# DM2097_Connector_B.net
KiCad netlist of a schematic drawn in Altium Designer
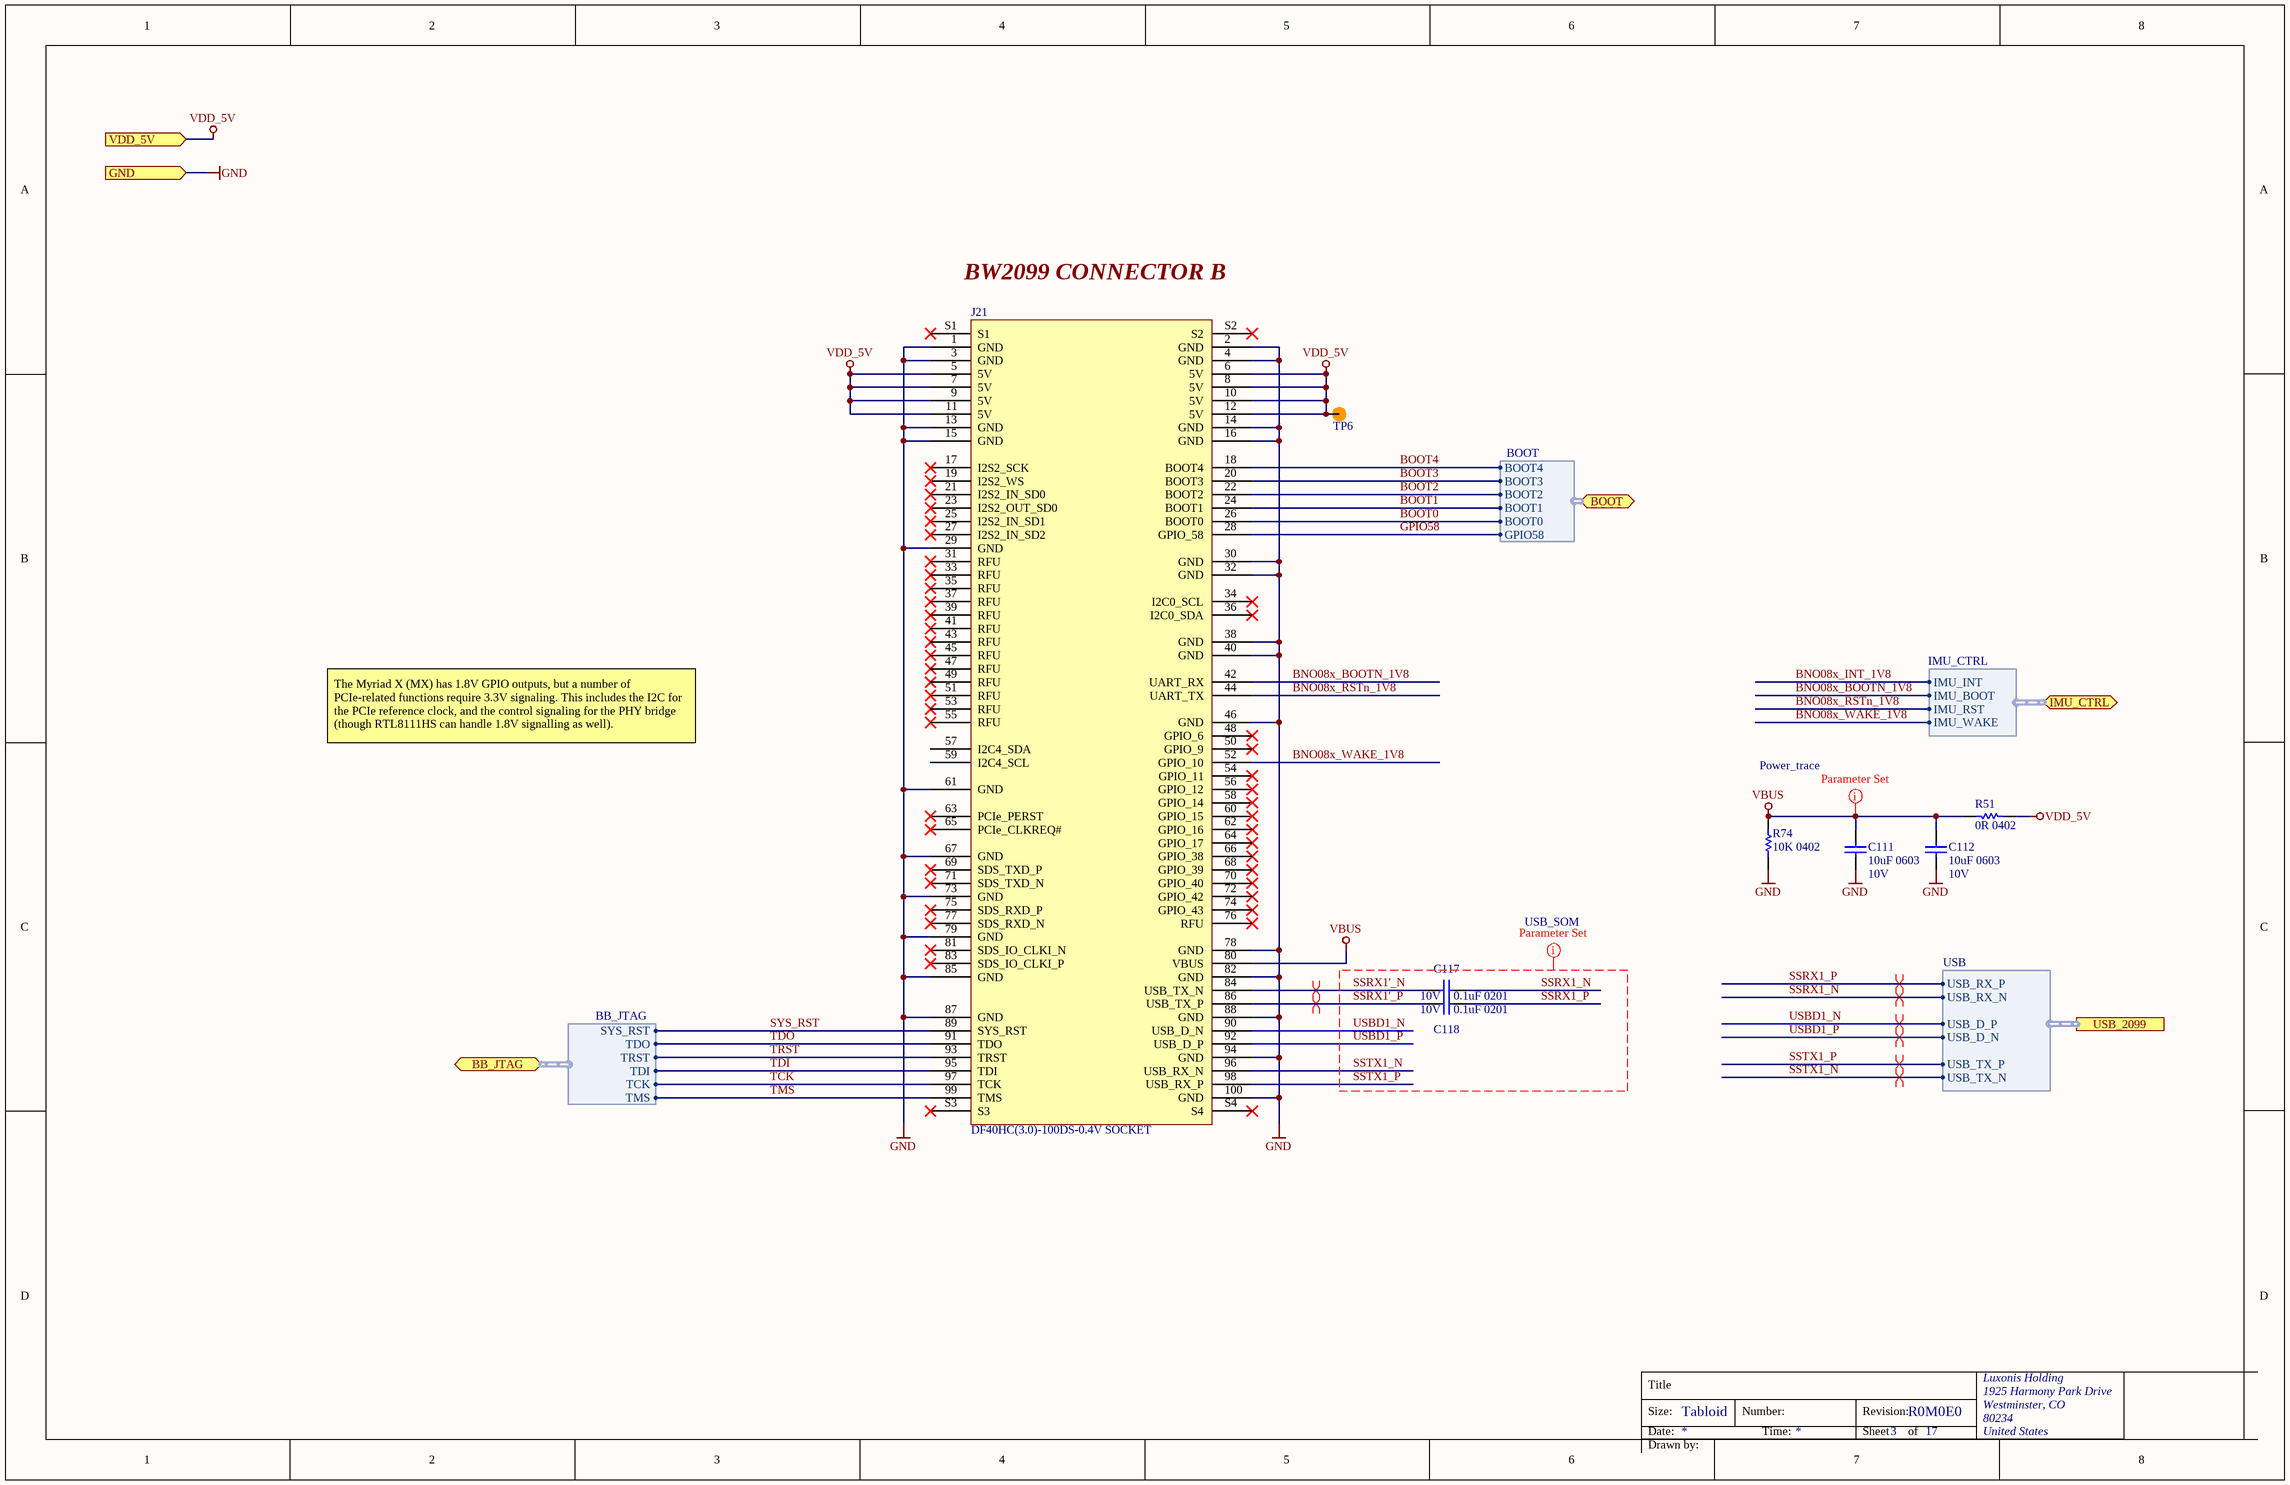
[diagram p0: DM2097_Connector_B.SchDoc]

(export (version "E")
  (design (tool "Eeschema 10.0.6"))
  (components
    (comp (ref "C111")
      (value "10uF 0603")
      (footprint "CAP_Altium_Vault_Generic:CAPC0603(1608)100_N")
      (description "CAP CER 10UF 10V X5R 0603 20%")
      (fields (field (name "TOLERANCE") "20%") (field (name "VOLTAGE RATING") "10V"))
      (libsource (lib "LuxonisMaster") (part "GRM188R61A106ME69D"))
    )
    (comp (ref "C112")
      (value "10uF 0603")
      (footprint "CAP_Altium_Vault_Generic:CAPC0603(1608)100_N")
      (description "CAP CER 10UF 10V X5R 0603 20%")
      (fields (field (name "TOLERANCE") "20%") (field (name "VOLTAGE RATING") "10V"))
      (libsource (lib "LuxonisMaster") (part "GRM188R61A106ME69D"))
    )
    (comp (ref "C117")
      (value "0.1uF 0201")
      (footprint "CAP_Altium_Vault_Generic:CAPC0201(0603)33_L")
      (description "CAP CER 0.1UF 10V X5R 0201")
      (fields (field (name "TOLERANCE") "10%") (field (name "VOLTAGE") "10V"))
      (libsource (lib "LuxonisMaster") (part "GRM033R61A104KE15D"))
    )
    (comp (ref "C118")
      (value "0.1uF 0201")
      (footprint "CAP_Altium_Vault_Generic:CAPC0201(0603)33_L")
      (description "CAP CER 0.1UF 10V X5R 0201")
      (fields (field (name "TOLERANCE") "10%") (field (name "VOLTAGE") "10V"))
      (libsource (lib "LuxonisMaster") (part "GRM033R61A104KE15D"))
    )
    (comp (ref "J21")
      (value "DF40HC(3.0)-100DS-0.4V SOCKET")
      (footprint "DF40HC-3.0-100DS-0.4V_minpad")
      (description "Conn Board to Board RCP 100 POS 0.4mm Solder ST SMD T/R")
      (libsource (lib "LuxonisMaster_OPAL") (part "BW2099_SCKT_Conn_B"))
    )
    (comp (ref "R51")
      (value "0R 0402")
      (footprint "RES_Altium_Vault_Generic:RESC0402(1005)_N")
      (description "RES SMD 0 OHM JUMPER 1/16W 0402")
      (fields (field (name "TOLERANCE") "5%"))
      (libsource (lib "LuxonisMaster") (part "CRCW04020000Z0ED"))
    )
    (comp (ref "R74")
      (value "10K 0402")
      (footprint "RES_Altium_Vault_Generic:RESC0402(1005)_N")
      (fields (field (name "TOLERANCE") "1%"))
      (libsource (lib "LuxonisMaster") (part "RC0402FR-1310KL"))
    )
    (comp (ref "TP6")
      (value "TP100_200_NS")
      (footprint "LuxonisMaster:TP100_200_NS")
      (libsource (lib "LuxonisMaster") (part "TEST_POINT"))
    )
  )
  (nets
    (net (code "5") (name "/BNO08x_BOOTN_1V8") (class "Default")
      (node (ref "J21") (pin "42") (pinfunction "UART_RX_42") (pintype "passive"))
    )
    (net (code "7") (name "/BNO08x_RSTn_1V8") (class "Default")
      (node (ref "J21") (pin "44") (pinfunction "UART_TX_44") (pintype "passive"))
    )
    (net (code "8") (name "/BNO08x_WAKE_1V8") (class "Default")
      (node (ref "J21") (pin "52") (pinfunction "GPIO_10_52") (pintype "passive"))
    )
    (net (code "9") (name "/BOOT0") (class "Default")
      (node (ref "J21") (pin "26") (pinfunction "BOOT0_26") (pintype "passive"))
    )
    (net (code "10") (name "/BOOT1") (class "Default")
      (node (ref "J21") (pin "24") (pinfunction "BOOT1_24") (pintype "passive"))
    )
    (net (code "11") (name "/BOOT2") (class "Default")
      (node (ref "J21") (pin "22") (pinfunction "BOOT2_22") (pintype "passive"))
    )
    (net (code "12") (name "/BOOT3") (class "Default")
      (node (ref "J21") (pin "20") (pinfunction "BOOT3_20") (pintype "passive"))
    )
    (net (code "13") (name "/BOOT4") (class "Default")
      (node (ref "J21") (pin "18") (pinfunction "BOOT4_18") (pintype "passive"))
    )
    (net (code "14") (name "/GPIO58") (class "Default")
      (node (ref "J21") (pin "28") (pinfunction "GPIO_58_28") (pintype "passive"))
    )
    (net (code "15") (name "/SSRX1'_N") (class "Default")
      (node (ref "C117") (pin "1") (pinfunction "1_1") (pintype "passive"))
      (node (ref "J21") (pin "84") (pinfunction "USB_TX_N_84") (pintype "passive"))
    )
    (net (code "16") (name "/SSRX1'_P") (class "Default")
      (node (ref "C118") (pin "1") (pinfunction "1_1") (pintype "passive"))
      (node (ref "J21") (pin "86") (pinfunction "USB_TX_P_86") (pintype "passive"))
    )
    (net (code "17") (name "/SSRX1_N") (class "Default")
      (node (ref "C117") (pin "2") (pinfunction "2_2") (pintype "passive"))
    )
    (net (code "18") (name "/SSRX1_P") (class "Default")
      (node (ref "C118") (pin "2") (pinfunction "2_2") (pintype "passive"))
    )
    (net (code "19") (name "/SSTX1_N") (class "Default")
      (node (ref "J21") (pin "96") (pinfunction "USB_RX_N_96") (pintype "passive"))
    )
    (net (code "20") (name "/SSTX1_P") (class "Default")
      (node (ref "J21") (pin "98") (pinfunction "USB_RX_P_98") (pintype "passive"))
    )
    (net (code "21") (name "/SYS_RST") (class "Default")
      (node (ref "J21") (pin "89") (pinfunction "SYS_RST_89") (pintype "passive"))
    )
    (net (code "22") (name "/TCK") (class "Default")
      (node (ref "J21") (pin "97") (pinfunction "TCK_97") (pintype "passive"))
    )
    (net (code "23") (name "/TDI") (class "Default")
      (node (ref "J21") (pin "95") (pinfunction "TDI_95") (pintype "passive"))
    )
    (net (code "24") (name "/TDO") (class "Default")
      (node (ref "J21") (pin "91") (pinfunction "TDO_91") (pintype "passive"))
    )
    (net (code "25") (name "/TMS") (class "Default")
      (node (ref "J21") (pin "99") (pinfunction "TMS_99") (pintype "passive"))
    )
    (net (code "26") (name "/TRST") (class "Default")
      (node (ref "J21") (pin "93") (pinfunction "TRST_93") (pintype "passive"))
    )
    (net (code "27") (name "/USBD1_N") (class "Default")
      (node (ref "J21") (pin "90") (pinfunction "USB_D_N_90") (pintype "passive"))
    )
    (net (code "28") (name "/USBD1_P") (class "Default")
      (node (ref "J21") (pin "92") (pinfunction "USB_D_P_92") (pintype "passive"))
    )
    (net (code "33") (name "GND") (class "Default")
      (node (ref "C111") (pin "1") (pinfunction "1_1") (pintype "passive"))
      (node (ref "C112") (pin "1") (pinfunction "1_1") (pintype "passive"))
      (node (ref "J21") (pin "1") (pinfunction "GND_1") (pintype "passive"))
      (node (ref "J21") (pin "100") (pinfunction "GND_100") (pintype "passive"))
      (node (ref "J21") (pin "13") (pinfunction "GND_13") (pintype "passive"))
      (node (ref "J21") (pin "14") (pinfunction "GND_14") (pintype "passive"))
      (node (ref "J21") (pin "15") (pinfunction "GND_15") (pintype "passive"))
      (node (ref "J21") (pin "16") (pinfunction "GND_16") (pintype "passive"))
      (node (ref "J21") (pin "2") (pinfunction "GND_2") (pintype "passive"))
      (node (ref "J21") (pin "29") (pinfunction "GND_29") (pintype "passive"))
      (node (ref "J21") (pin "3") (pinfunction "GND_3") (pintype "passive"))
      (node (ref "J21") (pin "30") (pinfunction "GND_30") (pintype "passive"))
      (node (ref "J21") (pin "32") (pinfunction "GND_32") (pintype "passive"))
      (node (ref "J21") (pin "38") (pinfunction "GND_38") (pintype "passive"))
      (node (ref "J21") (pin "4") (pinfunction "GND_4") (pintype "passive"))
      (node (ref "J21") (pin "40") (pinfunction "GND_40") (pintype "passive"))
      (node (ref "J21") (pin "46") (pinfunction "GND_46") (pintype "passive"))
      (node (ref "J21") (pin "61") (pinfunction "GND_61") (pintype "passive"))
      (node (ref "J21") (pin "67") (pinfunction "GND_67") (pintype "passive"))
      (node (ref "J21") (pin "73") (pinfunction "GND_73") (pintype "passive"))
      (node (ref "J21") (pin "78") (pinfunction "GND_78") (pintype "passive"))
      (node (ref "J21") (pin "79") (pinfunction "GND_79") (pintype "passive"))
      (node (ref "J21") (pin "82") (pinfunction "GND_82") (pintype "passive"))
      (node (ref "J21") (pin "85") (pinfunction "GND_85") (pintype "passive"))
      (node (ref "J21") (pin "87") (pinfunction "GND_87") (pintype "passive"))
      (node (ref "J21") (pin "88") (pinfunction "GND_88") (pintype "passive"))
      (node (ref "J21") (pin "94") (pinfunction "GND_94") (pintype "passive"))
      (node (ref "R74") (pin "1") (pinfunction "1_1") (pintype "passive"))
    )
    (net (code "34") (name "VBUS") (class "Default")
      (node (ref "C111") (pin "2") (pinfunction "2_2") (pintype "passive"))
      (node (ref "C112") (pin "2") (pinfunction "2_2") (pintype "passive"))
      (node (ref "J21") (pin "80") (pinfunction "VBUS_80") (pintype "passive"))
      (node (ref "R51") (pin "1") (pinfunction "1_1") (pintype "passive"))
      (node (ref "R74") (pin "2") (pinfunction "2_2") (pintype "passive"))
    )
    (net (code "35") (name "VDD_5V") (class "Default")
      (node (ref "J21") (pin "10") (pinfunction "5V_10") (pintype "passive"))
      (node (ref "J21") (pin "11") (pinfunction "5V_11") (pintype "passive"))
      (node (ref "J21") (pin "12") (pinfunction "5V_12") (pintype "passive"))
      (node (ref "J21") (pin "5") (pinfunction "5V_5") (pintype "passive"))
      (node (ref "J21") (pin "6") (pinfunction "5V_6") (pintype "passive"))
      (node (ref "J21") (pin "7") (pinfunction "5V_7") (pintype "passive"))
      (node (ref "J21") (pin "8") (pinfunction "5V_8") (pintype "passive"))
      (node (ref "J21") (pin "9") (pinfunction "5V_9") (pintype "passive"))
      (node (ref "R51") (pin "2") (pinfunction "2_2") (pintype "passive"))
      (node (ref "TP6") (pin "1") (pintype "passive"))
    )
    (net (code "36") (name "unconnected-(J21-GPIO_6-Pad48)") (class "Default")
      (node (ref "J21") (pin "48") (pinfunction "GPIO_6_48") (pintype "passive+no_connect"))
    )
    (net (code "37") (name "unconnected-(J21-GPIO_9-Pad50)") (class "Default")
      (node (ref "J21") (pin "50") (pinfunction "GPIO_9_50") (pintype "passive+no_connect"))
    )
    (net (code "38") (name "unconnected-(J21-GPIO_11-Pad54)") (class "Default")
      (node (ref "J21") (pin "54") (pinfunction "GPIO_11_54") (pintype "passive+no_connect"))
    )
    (net (code "39") (name "unconnected-(J21-GPIO_12-Pad56)") (class "Default")
      (node (ref "J21") (pin "56") (pinfunction "GPIO_12_56") (pintype "passive+no_connect"))
    )
    (net (code "40") (name "unconnected-(J21-GPIO_14-Pad58)") (class "Default")
      (node (ref "J21") (pin "58") (pinfunction "GPIO_14_58") (pintype "passive+no_connect"))
    )
    (net (code "41") (name "unconnected-(J21-GPIO_15-Pad60)") (class "Default")
      (node (ref "J21") (pin "60") (pinfunction "GPIO_15_60") (pintype "passive+no_connect"))
    )
    (net (code "42") (name "unconnected-(J21-GPIO_16-Pad62)") (class "Default")
      (node (ref "J21") (pin "62") (pinfunction "GPIO_16_62") (pintype "passive+no_connect"))
    )
    (net (code "43") (name "unconnected-(J21-GPIO_17-Pad64)") (class "Default")
      (node (ref "J21") (pin "64") (pinfunction "GPIO_17_64") (pintype "passive+no_connect"))
    )
    (net (code "44") (name "unconnected-(J21-GPIO_38-Pad66)") (class "Default")
      (node (ref "J21") (pin "66") (pinfunction "GPIO_38_66") (pintype "passive+no_connect"))
    )
    (net (code "45") (name "unconnected-(J21-GPIO_39-Pad68)") (class "Default")
      (node (ref "J21") (pin "68") (pinfunction "GPIO_39_68") (pintype "passive+no_connect"))
    )
    (net (code "46") (name "unconnected-(J21-GPIO_40-Pad70)") (class "Default")
      (node (ref "J21") (pin "70") (pinfunction "GPIO_40_70") (pintype "passive+no_connect"))
    )
    (net (code "47") (name "unconnected-(J21-GPIO_42-Pad72)") (class "Default")
      (node (ref "J21") (pin "72") (pinfunction "GPIO_42_72") (pintype "passive+no_connect"))
    )
    (net (code "48") (name "unconnected-(J21-GPIO_43-Pad74)") (class "Default")
      (node (ref "J21") (pin "74") (pinfunction "GPIO_43_74") (pintype "passive+no_connect"))
    )
    (net (code "49") (name "unconnected-(J21-I2C0_SCL-Pad34)") (class "Default")
      (node (ref "J21") (pin "34") (pinfunction "I2C0_SCL_34") (pintype "passive+no_connect"))
    )
    (net (code "50") (name "unconnected-(J21-I2C0_SDA-Pad36)") (class "Default")
      (node (ref "J21") (pin "36") (pinfunction "I2C0_SDA_36") (pintype "passive+no_connect"))
    )
    (net (code "51") (name "unconnected-(J21-I2C4_SCL-Pad59)") (class "Default")
      (node (ref "J21") (pin "59") (pinfunction "I2C4_SCL_59") (pintype "passive"))
    )
    (net (code "52") (name "unconnected-(J21-I2C4_SDA-Pad57)") (class "Default")
      (node (ref "J21") (pin "57") (pinfunction "I2C4_SDA_57") (pintype "passive"))
    )
    (net (code "53") (name "unconnected-(J21-I2S2_IN_SD0-Pad21)") (class "Default")
      (node (ref "J21") (pin "21") (pinfunction "I2S2_IN_SD0_21") (pintype "passive+no_connect"))
    )
    (net (code "54") (name "unconnected-(J21-I2S2_IN_SD1-Pad25)") (class "Default")
      (node (ref "J21") (pin "25") (pinfunction "I2S2_IN_SD1_25") (pintype "passive+no_connect"))
    )
    (net (code "55") (name "unconnected-(J21-I2S2_IN_SD2-Pad27)") (class "Default")
      (node (ref "J21") (pin "27") (pinfunction "I2S2_IN_SD2_27") (pintype "passive+no_connect"))
    )
    (net (code "56") (name "unconnected-(J21-I2S2_OUT_SD0-Pad23)") (class "Default")
      (node (ref "J21") (pin "23") (pinfunction "I2S2_OUT_SD0_23") (pintype "passive+no_connect"))
    )
    (net (code "57") (name "unconnected-(J21-I2S2_SCK-Pad17)") (class "Default")
      (node (ref "J21") (pin "17") (pinfunction "I2S2_SCK_17") (pintype "passive+no_connect"))
    )
    (net (code "58") (name "unconnected-(J21-I2S2_WS-Pad19)") (class "Default")
      (node (ref "J21") (pin "19") (pinfunction "I2S2_WS_19") (pintype "passive+no_connect"))
    )
    (net (code "59") (name "unconnected-(J21-PCIe_CLKREQ#-Pad65)") (class "Default")
      (node (ref "J21") (pin "65") (pinfunction "PCIe_CLKREQ#_65") (pintype "passive+no_connect"))
    )
    (net (code "60") (name "unconnected-(J21-PCIe_PERST-Pad63)") (class "Default")
      (node (ref "J21") (pin "63") (pinfunction "PCIe_PERST_63") (pintype "passive+no_connect"))
    )
    (net (code "61") (name "unconnected-(J21-PadS1)") (class "Default")
      (node (ref "J21") (pin "S1") (pinfunction "S1_S1") (pintype "passive+no_connect"))
    )
    (net (code "62") (name "unconnected-(J21-PadS2)") (class "Default")
      (node (ref "J21") (pin "S2") (pinfunction "S2_S2") (pintype "passive+no_connect"))
    )
    (net (code "63") (name "unconnected-(J21-PadS3)") (class "Default")
      (node (ref "J21") (pin "S3") (pinfunction "S3_S3") (pintype "passive+no_connect"))
    )
    (net (code "64") (name "unconnected-(J21-PadS4)") (class "Default")
      (node (ref "J21") (pin "S4") (pinfunction "S4_S4") (pintype "passive+no_connect"))
    )
    (net (code "65") (name "unconnected-(J21-RFU-Pad31)") (class "Default")
      (node (ref "J21") (pin "31") (pinfunction "RFU_31") (pintype "passive+no_connect"))
    )
    (net (code "66") (name "unconnected-(J21-RFU-Pad33)") (class "Default")
      (node (ref "J21") (pin "33") (pinfunction "RFU_33") (pintype "passive+no_connect"))
    )
    (net (code "67") (name "unconnected-(J21-RFU-Pad35)") (class "Default")
      (node (ref "J21") (pin "35") (pinfunction "RFU_35") (pintype "passive+no_connect"))
    )
    (net (code "68") (name "unconnected-(J21-RFU-Pad37)") (class "Default")
      (node (ref "J21") (pin "37") (pinfunction "RFU_37") (pintype "passive+no_connect"))
    )
    (net (code "69") (name "unconnected-(J21-RFU-Pad39)") (class "Default")
      (node (ref "J21") (pin "39") (pinfunction "RFU_39") (pintype "passive+no_connect"))
    )
    (net (code "70") (name "unconnected-(J21-RFU-Pad41)") (class "Default")
      (node (ref "J21") (pin "41") (pinfunction "RFU_41") (pintype "passive+no_connect"))
    )
    (net (code "71") (name "unconnected-(J21-RFU-Pad43)") (class "Default")
      (node (ref "J21") (pin "43") (pinfunction "RFU_43") (pintype "passive+no_connect"))
    )
    (net (code "72") (name "unconnected-(J21-RFU-Pad45)") (class "Default")
      (node (ref "J21") (pin "45") (pinfunction "RFU_45") (pintype "passive+no_connect"))
    )
    (net (code "73") (name "unconnected-(J21-RFU-Pad47)") (class "Default")
      (node (ref "J21") (pin "47") (pinfunction "RFU_47") (pintype "passive+no_connect"))
    )
    (net (code "74") (name "unconnected-(J21-RFU-Pad49)") (class "Default")
      (node (ref "J21") (pin "49") (pinfunction "RFU_49") (pintype "passive+no_connect"))
    )
    (net (code "75") (name "unconnected-(J21-RFU-Pad51)") (class "Default")
      (node (ref "J21") (pin "51") (pinfunction "RFU_51") (pintype "passive+no_connect"))
    )
    (net (code "76") (name "unconnected-(J21-RFU-Pad53)") (class "Default")
      (node (ref "J21") (pin "53") (pinfunction "RFU_53") (pintype "passive+no_connect"))
    )
    (net (code "77") (name "unconnected-(J21-RFU-Pad55)") (class "Default")
      (node (ref "J21") (pin "55") (pinfunction "RFU_55") (pintype "passive+no_connect"))
    )
    (net (code "78") (name "unconnected-(J21-RFU-Pad76)") (class "Default")
      (node (ref "J21") (pin "76") (pinfunction "RFU_76") (pintype "passive+no_connect"))
    )
    (net (code "79") (name "unconnected-(J21-SDS_IO_CLKI_N-Pad81)") (class "Default")
      (node (ref "J21") (pin "81") (pinfunction "SDS_IO_CLKI_N_81") (pintype "passive+no_connect"))
    )
    (net (code "80") (name "unconnected-(J21-SDS_IO_CLKI_P-Pad83)") (class "Default")
      (node (ref "J21") (pin "83") (pinfunction "SDS_IO_CLKI_P_83") (pintype "passive+no_connect"))
    )
    (net (code "81") (name "unconnected-(J21-SDS_RXD_N-Pad77)") (class "Default")
      (node (ref "J21") (pin "77") (pinfunction "SDS_RXD_N_77") (pintype "passive+no_connect"))
    )
    (net (code "82") (name "unconnected-(J21-SDS_RXD_P-Pad75)") (class "Default")
      (node (ref "J21") (pin "75") (pinfunction "SDS_RXD_P_75") (pintype "passive+no_connect"))
    )
    (net (code "83") (name "unconnected-(J21-SDS_TXD_N-Pad71)") (class "Default")
      (node (ref "J21") (pin "71") (pinfunction "SDS_TXD_N_71") (pintype "passive+no_connect"))
    )
    (net (code "84") (name "unconnected-(J21-SDS_TXD_P-Pad69)") (class "Default")
      (node (ref "J21") (pin "69") (pinfunction "SDS_TXD_P_69") (pintype "passive+no_connect"))
    )
  )
)
